# GSM_Velvet_Controller.net
KiCad netlist of a schematic drawn in Altium Designer
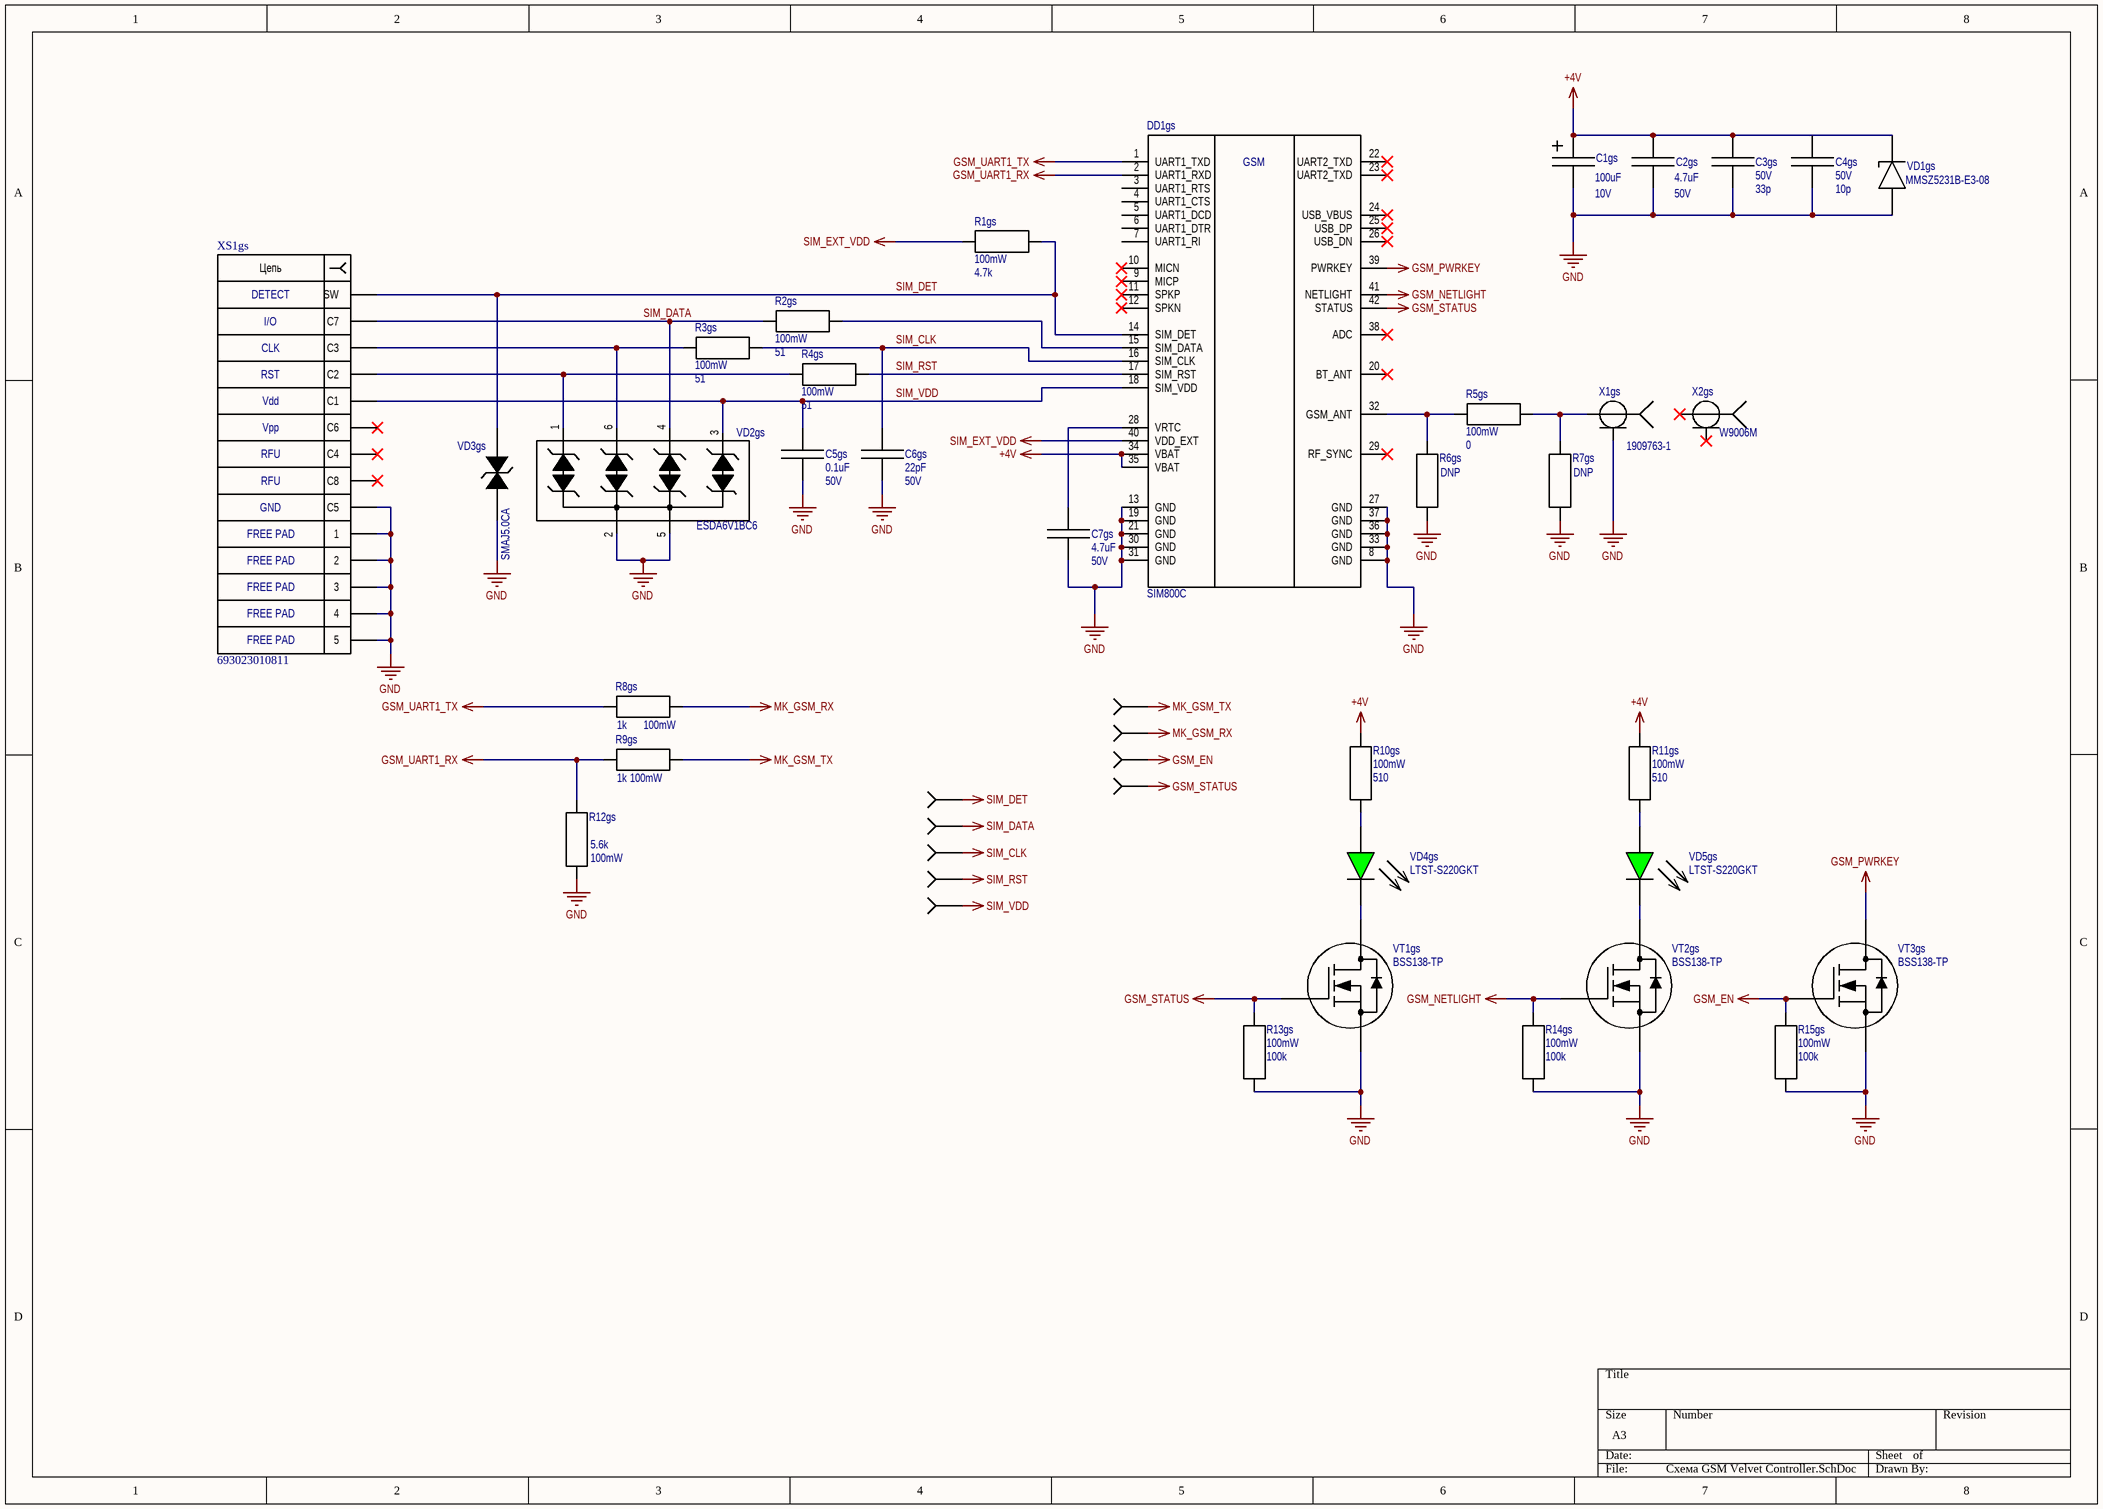
[diagram p0: Схема GSM Velvet Controller.SchDoc]

(export (version "E")
  (design (tool "Eeschema 10.0.6"))
  (components
    (comp (ref "C1gs")
      (value "TPSD107M010R0050")
      (footprint "CAP 2917 (D)")
      (description "CAP SMD TANT 100UF 20% 10V 2917")
      (fields
        (field (name "CAPACITANCE") "100uF")
        (field (name "TOLERANCE") "20%")
        (field (name "RATED VOLTAGE") "10V")
      )
      (libsource (lib "Passive components") (part "TPSD107M010R0050"))
    )
    (comp (ref "C2gs")
      (value "CL21A475KBQNNNE")
      (footprint "CAP 0805 IPC MAX")
      (description "CAP SMD CER 4.7UF 50V X5R 0805")
      (fields
        (field (name "TOLERANCE") "10%")
        (field (name "CAPACITANCE") "4.7uF")
        (field (name "RATED VOLTAGE") "50V")
      )
      (libsource (lib "Passive components") (part "CL21A475KBQNNNE"))
    )
    (comp (ref "C3gs")
      (value "C0603C330J5GAC7867")
      (footprint "CAP 0603 IPC MAX")
      (description "CAP SMD CER 33PF 50V C0G/NP0 0603")
      (fields
        (field (name "TOLERANCE") "5%")
        (field (name "RATED VOLTAGE") "50V")
        (field (name "CAPACITANCE") "33p")
      )
      (libsource (lib "Passive components") (part "C0603C330J5GAC7867"))
    )
    (comp (ref "C4gs")
      (value "CC0603JRNPO9BN100")
      (footprint "CAP 0603 IPC MAX")
      (description "CAP SMD CER 10PF 50V C0G/NP0 0603")
      (fields
        (field (name "TOLERANCE") "5%")
        (field (name "RATED VOLTAGE") "50V")
        (field (name "CAPACITANCE") "10p")
      )
      (libsource (lib "Passive components") (part "CC0603JRNPO9BN100"))
    )
    (comp (ref "C5gs")
      (value "GCM188R71H104KA57D")
      (footprint "CAP 0603 IPC MAX")
      (description "CAP SMD CER 0.1UF 50V X7R 0603")
      (fields
        (field (name "TOLERANCE") "10%")
        (field (name "CAPACITANCE") "0.1uF")
        (field (name "RATED VOLTAGE") "50V")
      )
      (libsource (lib "Passive components") (part "GCM188R71H104KA57D"))
    )
    (comp (ref "C6gs")
      (value "CC0603JRNPO9BN220")
      (footprint "CAP 0603 IPC MAX")
      (description "CAP SMD CER 22PF 50V NP0  0603")
      (fields
        (field (name "TOLERANCE") "5%")
        (field (name "CAPACITANCE") "22pF")
        (field (name "RATED VOLTAGE") "50V")
      )
      (libsource (lib "Passive components") (part "CC0603JRNPO9BN220"))
    )
    (comp (ref "C7gs")
      (value "CL21A475KBQNNNE")
      (footprint "CAP 0805 IPC MAX")
      (description "CAP SMD CER 4.7UF 50V X5R 0805")
      (fields
        (field (name "TOLERANCE") "10%")
        (field (name "CAPACITANCE") "4.7uF")
        (field (name "RATED VOLTAGE") "50V")
      )
      (libsource (lib "Passive components") (part "CL21A475KBQNNNE"))
    )
    (comp (ref "DD1gs")
      (value "SIM800C")
      (footprint "SIM-800C")
      (description "GSM/GPRS Module")
      (libsource (lib "Digital") (part "SIM800C"))
    )
    (comp (ref "R1gs")
      (value "RMCF0603FT4K70")
      (footprint "RES 0603 IPC MAX")
      (description "RES SMD 4.7k OHM 1% 1/10W 0603")
      (fields
        (field (name "TOLERANCE") "1%")
        (field (name "RATED POWER") "100mW")
        (field (name "RESISTANCE") "4.7k")
      )
      (libsource (lib "Passive components") (part "RMCF0603FT4K70"))
    )
    (comp (ref "R2gs")
      (value "RMCF0603FT51R0")
      (footprint "RES 0603 IPC MAX")
      (description "RES SMD 51 OHM 1% 1/10W 0603")
      (fields
        (field (name "TOLERANCE") "1%")
        (field (name "RATED POWER") "100mW")
        (field (name "RESISTANCE") "51")
      )
      (libsource (lib "Passive components") (part "RMCF0603FT51R0"))
    )
    (comp (ref "R3gs")
      (value "RMCF0603FT51R0")
      (footprint "RES 0603 IPC MAX")
      (description "RES SMD 51 OHM 1% 1/10W 0603")
      (fields
        (field (name "TOLERANCE") "1%")
        (field (name "RATED POWER") "100mW")
        (field (name "RESISTANCE") "51")
      )
      (libsource (lib "Passive components") (part "RMCF0603FT51R0"))
    )
    (comp (ref "R4gs")
      (value "RMCF0603FT51R0")
      (footprint "RES 0603 IPC MAX")
      (description "RES SMD 51 OHM 1% 1/10W 0603")
      (fields
        (field (name "TOLERANCE") "1%")
        (field (name "RATED POWER") "100mW")
        (field (name "RESISTANCE") "51")
      )
      (libsource (lib "Passive components") (part "RMCF0603FT51R0"))
    )
    (comp (ref "R5gs")
      (value "RMCF0603ZT0R00")
      (footprint "RES 0603 IPC MAX")
      (description "RES SMD 0 OHM 1% 1/10W 0603")
      (fields
        (field (name "TOLERANCE") "1%")
        (field (name "RATED POWER") "100mW")
        (field (name "RESISTANCE") "0")
      )
      (libsource (lib "Passive components") (part "RMCF0603ZT0R00"))
    )
    (comp (ref "R6gs")
      (value "DNP")
      (footprint "RES 0603 IPC MAX")
      (description "RES SMD/TH ?R (&K) OHM ?% ?W (PACKAGE)")
      (libsource (lib "Passive components") (part "RES GOST"))
    )
    (comp (ref "R7gs")
      (value "DNP")
      (footprint "RES 0603 IPC MAX")
      (description "RES SMD/TH ?R (&K) OHM ?% ?W (PACKAGE)")
      (libsource (lib "Passive components") (part "RES GOST"))
    )
    (comp (ref "R8gs")
      (value "RMCF0603FT1K00")
      (footprint "RES 0603 IPC MAX")
      (description "RES SMD 1K OHM 1% 1/10W 0603")
      (fields
        (field (name "RESISTANCE") "1k")
        (field (name "TOLERANCE") "1%")
        (field (name "RATED POWER") "100mW")
      )
      (libsource (lib "Passive components") (part "RMCF0603FT1K00"))
    )
    (comp (ref "R9gs")
      (value "RMCF0603FT1K00")
      (footprint "RES 0603 IPC MAX")
      (description "RES SMD 1K OHM 1% 1/10W 0603")
      (fields
        (field (name "RESISTANCE") "1k")
        (field (name "TOLERANCE") "1%")
        (field (name "RATED POWER") "100mW")
      )
      (libsource (lib "Passive components") (part "RMCF0603FT1K00"))
    )
    (comp (ref "R10gs")
      (value "RMCF0603JT510R")
      (footprint "RES 0603 IPC MAX")
      (description "RES SMD 510 OHM 5% 1/10W 0603")
      (fields
        (field (name "TOLERANCE") "5%")
        (field (name "POWER RATED") "100mW")
        (field (name "RESISTANCE") "510")
      )
      (libsource (lib "Passive components") (part "RMCF0603JT510R"))
    )
    (comp (ref "R11gs")
      (value "RMCF0603JT510R")
      (footprint "RES 0603 IPC MAX")
      (description "RES SMD 510 OHM 5% 1/10W 0603")
      (fields
        (field (name "TOLERANCE") "5%")
        (field (name "POWER RATED") "100mW")
        (field (name "RESISTANCE") "510")
      )
      (libsource (lib "Passive components") (part "RMCF0603JT510R"))
    )
    (comp (ref "R12gs")
      (value "RMCF0603FT5K60")
      (footprint "RES 0603 IPC MAX")
      (description "RES SMD 5.6K OHM 1% 1/10W 0603")
      (fields
        (field (name "RESISTANCE") "5.6k")
        (field (name "TOLERANCE") "1%")
        (field (name "RATED POWER") "100mW")
      )
      (libsource (lib "Passive components") (part "RMCF0603FT5K60"))
    )
    (comp (ref "R13gs")
      (value "RMCF0603FT100K")
      (footprint "RES 0603 IPC MAX")
      (description "RES SMD 100K OHM 5% 1/10W 0603")
      (fields
        (field (name "TOLERANCE") "5%")
        (field (name "POWER RATED") "100mW")
        (field (name "RESISTANCE") "100k")
      )
      (libsource (lib "Passive components") (part "RMCF0603FT100K"))
    )
    (comp (ref "R14gs")
      (value "RMCF0603FT100K")
      (footprint "RES 0603 IPC MAX")
      (description "RES SMD 100K OHM 5% 1/10W 0603")
      (fields
        (field (name "TOLERANCE") "5%")
        (field (name "POWER RATED") "100mW")
        (field (name "RESISTANCE") "100k")
      )
      (libsource (lib "Passive components") (part "RMCF0603FT100K"))
    )
    (comp (ref "R15gs")
      (value "RMCF0603FT100K")
      (footprint "RES 0603 IPC MAX")
      (description "RES SMD 100K OHM 5% 1/10W 0603")
      (fields
        (field (name "TOLERANCE") "5%")
        (field (name "POWER RATED") "100mW")
        (field (name "RESISTANCE") "100k")
      )
      (libsource (lib "Passive components") (part "RMCF0603FT100K"))
    )
    (comp (ref "TP2gs")
      (value "1.2MM TP")
      (footprint "TESTPOINT 1.2mm")
      (libsource (lib "Connectors") (part "Testpoint 1.2mm"))
    )
    (comp (ref "TP4gs")
      (value "1.2MM TP")
      (footprint "TESTPOINT 1.2mm")
      (libsource (lib "Connectors") (part "Testpoint 1.2mm"))
    )
    (comp (ref "TP5gs")
      (value "1.2MM TP")
      (footprint "TESTPOINT 1.2mm")
      (libsource (lib "Connectors") (part "Testpoint 1.2mm"))
    )
    (comp (ref "TP6gs")
      (value "1.2MM TP")
      (footprint "TESTPOINT 1.2mm")
      (libsource (lib "Connectors") (part "Testpoint 1.2mm"))
    )
    (comp (ref "TP7gs")
      (value "1.2MM TP")
      (footprint "TESTPOINT 1.2mm")
      (libsource (lib "Connectors") (part "Testpoint 1.2mm"))
    )
    (comp (ref "TP9gs")
      (value "1.2MM TP")
      (footprint "TESTPOINT 1.2mm")
      (libsource (lib "Connectors") (part "Testpoint 1.2mm"))
    )
    (comp (ref "TP10gs")
      (value "1.2MM TP")
      (footprint "TESTPOINT 1.2mm")
      (libsource (lib "Connectors") (part "Testpoint 1.2mm"))
    )
    (comp (ref "TP11gs")
      (value "1.2MM TP")
      (footprint "TESTPOINT 1.2mm")
      (libsource (lib "Connectors") (part "Testpoint 1.2mm"))
    )
    (comp (ref "TP12gs")
      (value "1.2MM TP")
      (footprint "TESTPOINT 1.2mm")
      (libsource (lib "Connectors") (part "Testpoint 1.2mm"))
    )
    (comp (ref "VD1gs")
      (value "MMSZ5231B-E3-08")
      (footprint "SOD-123 (Marked)")
      (description "DIODE ZENER 5.1V 500MW SOD123")
      (fields (field (name "TOLERANCE") "5%"))
      (libsource (lib "Diodes") (part "MMSZ5231B-E3-08"))
    )
    (comp (ref "VD2gs")
      (value "ESDA6V1BC6")
      (footprint "SOT-23-6")
      (description "TVS DIODE 5VWM SOT23-6")
      (libsource (lib "Diodes") (part "ESDA6V1BC6"))
    )
    (comp (ref "VD3gs")
      (value "SMAJ5.0CA")
      (footprint "DO-214AC Bidirectional")
      (description "TVS DIODE 5VWM 9.2VC DO214AC")
      (libsource (lib "Diodes") (part "SMAJ5.0CA"))
    )
    (comp (ref "VD4gs")
      (value "LTST-S220GKT")
      (footprint "0805 DIODE")
      (description "LED GREEN CLEAR SMD R/A")
      (libsource (lib "Diodes") (part "LTST-S220GKT"))
    )
    (comp (ref "VD5gs")
      (value "LTST-S220GKT")
      (footprint "0805 DIODE")
      (description "LED GREEN CLEAR SMD R/A")
      (libsource (lib "Diodes") (part "LTST-S220GKT"))
    )
    (comp (ref "VT1gs")
      (value "BSS138-TP")
      (footprint "SOT-23-3")
      (description "MOSFET N-CH 50V 220MA SOT23")
      (libsource (lib "MOSFET") (part "BSS138-TP"))
    )
    (comp (ref "VT2gs")
      (value "BSS138-TP")
      (footprint "SOT-23-3")
      (description "MOSFET N-CH 50V 220MA SOT23")
      (libsource (lib "MOSFET") (part "BSS138-TP"))
    )
    (comp (ref "VT3gs")
      (value "BSS138-TP")
      (footprint "SOT-23-3")
      (description "MOSFET N-CH 50V 220MA SOT23")
      (libsource (lib "MOSFET") (part "BSS138-TP"))
    )
    (comp (ref "X1gs")
      (value "1909763-1")
      (footprint "1909763-1")
      (description "CONN UMCC JACK STR 50OHM SMD")
      (libsource (lib "Connectors") (part "1909763-1"))
    )
    (comp (ref "X2gs")
      (value "W9006M")
      (description "CABLE ASSY 6\" SMA FM TO I-PEX")
      (libsource (lib "Connectors") (part "W9006M"))
    )
    (comp (ref "XS1gs")
      (value "693023010811")
      (footprint "693023010811")
      (description "CONN SMART CARD")
      (libsource (lib "Connectors") (part "693023010811"))
    )
  )
  (nets
    (net (code "1") (name "+4V") (class "Default")
      (node (ref "C1gs") (pin "1") (pinfunction "1_1") (pintype "passive"))
      (node (ref "C2gs") (pin "1") (pinfunction "1_1") (pintype "passive"))
      (node (ref "C3gs") (pin "1") (pinfunction "1_1") (pintype "passive"))
      (node (ref "C4gs") (pin "1") (pinfunction "1_1") (pintype "passive"))
      (node (ref "DD1gs") (pin "34") (pinfunction "VBAT_34") (pintype "passive"))
      (node (ref "DD1gs") (pin "35") (pinfunction "VBAT_35") (pintype "passive"))
      (node (ref "R10gs") (pin "2") (pinfunction "2_2") (pintype "passive"))
      (node (ref "R11gs") (pin "2") (pinfunction "2_2") (pintype "passive"))
      (node (ref "VD1gs") (pin "1") (pinfunction "1_1") (pintype "passive"))
    )
    (net (code "2") (name "GND") (class "Default")
      (node (ref "C1gs") (pin "2") (pinfunction "2_2") (pintype "passive"))
      (node (ref "C2gs") (pin "2") (pinfunction "2_2") (pintype "passive"))
      (node (ref "C3gs") (pin "2") (pinfunction "2_2") (pintype "passive"))
      (node (ref "C4gs") (pin "2") (pinfunction "2_2") (pintype "passive"))
      (node (ref "C5gs") (pin "2") (pinfunction "2_2") (pintype "passive"))
      (node (ref "C6gs") (pin "2") (pinfunction "2_2") (pintype "passive"))
      (node (ref "C7gs") (pin "2") (pinfunction "2_2") (pintype "passive"))
      (node (ref "DD1gs") (pin "13") (pinfunction "GND_13") (pintype "passive"))
      (node (ref "DD1gs") (pin "19") (pinfunction "GND_19") (pintype "passive"))
      (node (ref "DD1gs") (pin "21") (pinfunction "GND_21") (pintype "passive"))
      (node (ref "DD1gs") (pin "27") (pinfunction "GND_27") (pintype "passive"))
      (node (ref "DD1gs") (pin "30") (pinfunction "GND_30") (pintype "passive"))
      (node (ref "DD1gs") (pin "31") (pinfunction "GND_31") (pintype "passive"))
      (node (ref "DD1gs") (pin "33") (pinfunction "GND_33") (pintype "passive"))
      (node (ref "DD1gs") (pin "36") (pinfunction "GND_36") (pintype "passive"))
      (node (ref "DD1gs") (pin "37") (pinfunction "GND_37") (pintype "passive"))
      (node (ref "DD1gs") (pin "8") (pinfunction "GND_8") (pintype "passive"))
      (node (ref "R12gs") (pin "1") (pinfunction "1_1") (pintype "passive"))
      (node (ref "R13gs") (pin "1") (pinfunction "1_1") (pintype "passive"))
      (node (ref "R14gs") (pin "1") (pinfunction "1_1") (pintype "passive"))
      (node (ref "R15gs") (pin "1") (pinfunction "1_1") (pintype "passive"))
      (node (ref "R6gs") (pin "1") (pinfunction "1_1") (pintype "passive"))
      (node (ref "R7gs") (pin "1") (pinfunction "1_1") (pintype "passive"))
      (node (ref "VD1gs") (pin "2") (pinfunction "2_2") (pintype "passive"))
      (node (ref "VD2gs") (pin "2") (pinfunction "2_2") (pintype "passive"))
      (node (ref "VD2gs") (pin "5") (pinfunction "5_5") (pintype "passive"))
      (node (ref "VD3gs") (pin "1") (pinfunction "1_1") (pintype "passive"))
      (node (ref "VT1gs") (pin "2") (pinfunction "S_2") (pintype "passive"))
      (node (ref "VT2gs") (pin "2") (pinfunction "S_2") (pintype "passive"))
      (node (ref "VT3gs") (pin "2") (pinfunction "S_2") (pintype "passive"))
      (node (ref "X1gs") (pin "2") (pinfunction "2_2") (pintype "passive"))
      (node (ref "XS1gs") (pin "1") (pinfunction "1_1") (pintype "passive"))
      (node (ref "XS1gs") (pin "2") (pinfunction "2_2") (pintype "passive"))
      (node (ref "XS1gs") (pin "3") (pinfunction "3_3") (pintype "passive"))
      (node (ref "XS1gs") (pin "4") (pinfunction "4_4") (pintype "passive"))
      (node (ref "XS1gs") (pin "5") (pinfunction "5_5") (pintype "passive"))
      (node (ref "XS1gs") (pin "C5") (pinfunction "C5_C5") (pintype "passive"))
    )
    (net (code "3") (name "GSM_EN") (class "Default")
      (node (ref "R15gs") (pin "2") (pinfunction "2_2") (pintype "passive"))
      (node (ref "TP5gs") (pin "1") (pinfunction "1_1") (pintype "passive"))
      (node (ref "VT3gs") (pin "1") (pinfunction "G_1") (pintype "passive"))
    )
    (net (code "4") (name "GSM_NETLIGHT") (class "Default")
      (node (ref "DD1gs") (pin "41") (pinfunction "NETLIGHT_41") (pintype "passive"))
      (node (ref "R14gs") (pin "2") (pinfunction "2_2") (pintype "passive"))
      (node (ref "VT2gs") (pin "1") (pinfunction "G_1") (pintype "passive"))
    )
    (net (code "5") (name "GSM_PWRKEY") (class "Default")
      (node (ref "DD1gs") (pin "39") (pinfunction "PWRKEY_39") (pintype "passive"))
      (node (ref "VT3gs") (pin "3") (pinfunction "D_3") (pintype "passive"))
    )
    (net (code "6") (name "GSM_STATUS") (class "Default")
      (node (ref "DD1gs") (pin "42") (pinfunction "STATUS_42") (pintype "passive"))
      (node (ref "R13gs") (pin "2") (pinfunction "2_2") (pintype "passive"))
      (node (ref "TP6gs") (pin "1") (pinfunction "1_1") (pintype "passive"))
      (node (ref "VT1gs") (pin "1") (pinfunction "G_1") (pintype "passive"))
    )
    (net (code "7") (name "GSM_UART1_RX") (class "Default")
      (node (ref "DD1gs") (pin "2") (pinfunction "UART1_RXD_2") (pintype "passive"))
      (node (ref "R12gs") (pin "2") (pinfunction "2_2") (pintype "passive"))
      (node (ref "R9gs") (pin "1") (pinfunction "1_1") (pintype "passive"))
    )
    (net (code "8") (name "GSM_UART1_TX") (class "Default")
      (node (ref "DD1gs") (pin "1") (pinfunction "UART1_TXD_1") (pintype "passive"))
      (node (ref "R8gs") (pin "1") (pinfunction "1_1") (pintype "passive"))
    )
    (net (code "9") (name "MK_GSM_RX") (class "Default")
      (node (ref "R8gs") (pin "2") (pinfunction "2_2") (pintype "passive"))
      (node (ref "TP4gs") (pin "1") (pinfunction "1_1") (pintype "passive"))
    )
    (net (code "10") (name "MK_GSM_TX") (class "Default")
      (node (ref "R9gs") (pin "2") (pinfunction "2_2") (pintype "passive"))
      (node (ref "TP2gs") (pin "1") (pinfunction "1_1") (pintype "passive"))
    )
    (net (code "11") (name "Net-(DD1gs-GSM_ANT)") (class "Default")
      (node (ref "DD1gs") (pin "32") (pinfunction "GSM_ANT_32") (pintype "passive"))
      (node (ref "R5gs") (pin "1") (pinfunction "1_1") (pintype "passive"))
      (node (ref "R6gs") (pin "2") (pinfunction "2_2") (pintype "passive"))
    )
    (net (code "12") (name "Net-(DD1gs-SIM_DATA)") (class "Default")
      (node (ref "DD1gs") (pin "15") (pinfunction "SIM_DATA_15") (pintype "passive"))
      (node (ref "R2gs") (pin "2") (pinfunction "2_2") (pintype "passive"))
    )
    (net (code "13") (name "Net-(DD1gs-VRTC)") (class "Default")
      (node (ref "C7gs") (pin "1") (pinfunction "1_1") (pintype "passive"))
      (node (ref "DD1gs") (pin "28") (pinfunction "VRTC_28") (pintype "passive"))
    )
    (net (code "14") (name "Net-(R3gs-Pad1)") (class "Default")
      (node (ref "R3gs") (pin "1") (pinfunction "1_1") (pintype "passive"))
      (node (ref "VD2gs") (pin "6") (pinfunction "6_6") (pintype "passive"))
      (node (ref "XS1gs") (pin "C3") (pinfunction "C3_C3") (pintype "passive"))
    )
    (net (code "15") (name "Net-(R4gs-Pad1)") (class "Default")
      (node (ref "R4gs") (pin "1") (pinfunction "1_1") (pintype "passive"))
      (node (ref "VD2gs") (pin "1") (pinfunction "1_1") (pintype "passive"))
      (node (ref "XS1gs") (pin "C2") (pinfunction "C2_C2") (pintype "passive"))
    )
    (net (code "16") (name "Net-(R5gs-Pad2)") (class "Default")
      (node (ref "R5gs") (pin "2") (pinfunction "2_2") (pintype "passive"))
      (node (ref "R7gs") (pin "2") (pinfunction "2_2") (pintype "passive"))
      (node (ref "X1gs") (pin "1") (pinfunction "1_1") (pintype "passive"))
    )
    (net (code "17") (name "Net-(R10gs-Pad1)") (class "Default")
      (node (ref "R10gs") (pin "1") (pinfunction "1_1") (pintype "passive"))
      (node (ref "VD4gs") (pin "1") (pinfunction "1_1") (pintype "passive"))
    )
    (net (code "18") (name "Net-(R11gs-Pad1)") (class "Default")
      (node (ref "R11gs") (pin "1") (pinfunction "1_1") (pintype "passive"))
      (node (ref "VD5gs") (pin "1") (pinfunction "1_1") (pintype "passive"))
    )
    (net (code "19") (name "Net-(VT1gs-D)") (class "Default")
      (node (ref "VD4gs") (pin "2") (pinfunction "2_2") (pintype "passive"))
      (node (ref "VT1gs") (pin "3") (pinfunction "D_3") (pintype "passive"))
    )
    (net (code "20") (name "Net-(VT2gs-D)") (class "Default")
      (node (ref "VD5gs") (pin "2") (pinfunction "2_2") (pintype "passive"))
      (node (ref "VT2gs") (pin "3") (pinfunction "D_3") (pintype "passive"))
    )
    (net (code "21") (name "SIM_CLK") (class "Default")
      (node (ref "C6gs") (pin "1") (pinfunction "1_1") (pintype "passive"))
      (node (ref "DD1gs") (pin "16") (pinfunction "SIM_CLK_16") (pintype "passive"))
      (node (ref "R3gs") (pin "2") (pinfunction "2_2") (pintype "passive"))
      (node (ref "TP10gs") (pin "1") (pinfunction "1_1") (pintype "passive"))
    )
    (net (code "22") (name "SIM_DATA") (class "Default")
      (node (ref "R2gs") (pin "1") (pinfunction "1_1") (pintype "passive"))
      (node (ref "TP9gs") (pin "1") (pinfunction "1_1") (pintype "passive"))
      (node (ref "VD2gs") (pin "4") (pinfunction "4_4") (pintype "passive"))
      (node (ref "XS1gs") (pin "C7") (pinfunction "C7_C7") (pintype "passive"))
    )
    (net (code "23") (name "SIM_DET") (class "Default")
      (node (ref "DD1gs") (pin "14") (pinfunction "SIM_DET_14") (pintype "passive"))
      (node (ref "R1gs") (pin "2") (pinfunction "2_2") (pintype "passive"))
      (node (ref "TP7gs") (pin "1") (pinfunction "1_1") (pintype "passive"))
      (node (ref "VD3gs") (pin "2") (pinfunction "2_2") (pintype "passive"))
      (node (ref "XS1gs") (pin "SW") (pinfunction "SW_SW") (pintype "passive"))
    )
    (net (code "24") (name "SIM_EXT_VDD") (class "Default")
      (node (ref "DD1gs") (pin "40") (pinfunction "VDD_EXT_40") (pintype "passive"))
      (node (ref "R1gs") (pin "1") (pinfunction "1_1") (pintype "passive"))
    )
    (net (code "25") (name "SIM_RST") (class "Default")
      (node (ref "DD1gs") (pin "17") (pinfunction "SIM_RST_17") (pintype "passive"))
      (node (ref "R4gs") (pin "2") (pinfunction "2_2") (pintype "passive"))
      (node (ref "TP11gs") (pin "1") (pinfunction "1_1") (pintype "passive"))
    )
    (net (code "26") (name "SIM_VDD") (class "Default")
      (node (ref "C5gs") (pin "1") (pinfunction "1_1") (pintype "passive"))
      (node (ref "DD1gs") (pin "18") (pinfunction "SIM_VDD_18") (pintype "passive"))
      (node (ref "TP12gs") (pin "1") (pinfunction "1_1") (pintype "passive"))
      (node (ref "VD2gs") (pin "3") (pinfunction "3_3") (pintype "passive"))
      (node (ref "XS1gs") (pin "C1") (pinfunction "C1_C1") (pintype "passive"))
    )
    (net (code "27") (name "unconnected-(DD1gs-ADC-Pad38)") (class "Default")
      (node (ref "DD1gs") (pin "38") (pinfunction "ADC_38") (pintype "passive+no_connect"))
    )
    (net (code "28") (name "unconnected-(DD1gs-BT_ANT-Pad20)") (class "Default")
      (node (ref "DD1gs") (pin "20") (pinfunction "BT_ANT_20") (pintype "passive+no_connect"))
    )
    (net (code "29") (name "unconnected-(DD1gs-MICN-Pad10)") (class "Default")
      (node (ref "DD1gs") (pin "10") (pinfunction "MICN_10") (pintype "passive+no_connect"))
    )
    (net (code "30") (name "unconnected-(DD1gs-MICP-Pad9)") (class "Default")
      (node (ref "DD1gs") (pin "9") (pinfunction "MICP_9") (pintype "passive+no_connect"))
    )
    (net (code "31") (name "unconnected-(DD1gs-RF_SYNC-Pad29)") (class "Default")
      (node (ref "DD1gs") (pin "29") (pinfunction "RF_SYNC_29") (pintype "passive+no_connect"))
    )
    (net (code "32") (name "unconnected-(DD1gs-SPKN-Pad12)") (class "Default")
      (node (ref "DD1gs") (pin "12") (pinfunction "SPKN_12") (pintype "passive+no_connect"))
    )
    (net (code "33") (name "unconnected-(DD1gs-SPKP-Pad11)") (class "Default")
      (node (ref "DD1gs") (pin "11") (pinfunction "SPKP_11") (pintype "passive+no_connect"))
    )
    (net (code "34") (name "unconnected-(DD1gs-UART1_CTS-Pad4)") (class "Default")
      (node (ref "DD1gs") (pin "4") (pinfunction "UART1_CTS_4") (pintype "passive"))
    )
    (net (code "35") (name "unconnected-(DD1gs-UART1_DCD-Pad5)") (class "Default")
      (node (ref "DD1gs") (pin "5") (pinfunction "UART1_DCD_5") (pintype "passive"))
    )
    (net (code "36") (name "unconnected-(DD1gs-UART1_DTR-Pad6)") (class "Default")
      (node (ref "DD1gs") (pin "6") (pinfunction "UART1_DTR_6") (pintype "passive"))
    )
    (net (code "37") (name "unconnected-(DD1gs-UART1_RI-Pad7)") (class "Default")
      (node (ref "DD1gs") (pin "7") (pinfunction "UART1_RI_7") (pintype "passive"))
    )
    (net (code "38") (name "unconnected-(DD1gs-UART1_RTS-Pad3)") (class "Default")
      (node (ref "DD1gs") (pin "3") (pinfunction "UART1_RTS_3") (pintype "passive"))
    )
    (net (code "39") (name "unconnected-(DD1gs-UART2_TXD-Pad22)") (class "Default")
      (node (ref "DD1gs") (pin "22") (pinfunction "UART2_TXD_22") (pintype "passive+no_connect"))
    )
    (net (code "40") (name "unconnected-(DD1gs-UART2_TXD-Pad23)") (class "Default")
      (node (ref "DD1gs") (pin "23") (pinfunction "UART2_TXD_23") (pintype "passive+no_connect"))
    )
    (net (code "41") (name "unconnected-(DD1gs-USB_DN-Pad26)") (class "Default")
      (node (ref "DD1gs") (pin "26") (pinfunction "USB_DN_26") (pintype "passive+no_connect"))
    )
    (net (code "42") (name "unconnected-(DD1gs-USB_DP-Pad25)") (class "Default")
      (node (ref "DD1gs") (pin "25") (pinfunction "USB_DP_25") (pintype "passive+no_connect"))
    )
    (net (code "43") (name "unconnected-(DD1gs-USB_VBUS-Pad24)") (class "Default")
      (node (ref "DD1gs") (pin "24") (pinfunction "USB_VBUS_24") (pintype "passive+no_connect"))
    )
    (net (code "44") (name "unconnected-(X2gs-Pad1)") (class "Default")
      (node (ref "X2gs") (pin "1") (pinfunction "1_1") (pintype "passive+no_connect"))
    )
    (net (code "45") (name "unconnected-(X2gs-Pad2)") (class "Default")
      (node (ref "X2gs") (pin "2") (pinfunction "2_2") (pintype "passive+no_connect"))
    )
    (net (code "46") (name "unconnected-(XS1gs-PadC4)") (class "Default")
      (node (ref "XS1gs") (pin "C4") (pinfunction "C4_C4") (pintype "passive+no_connect"))
    )
    (net (code "47") (name "unconnected-(XS1gs-PadC6)") (class "Default")
      (node (ref "XS1gs") (pin "C6") (pinfunction "C6_C6") (pintype "passive+no_connect"))
    )
    (net (code "48") (name "unconnected-(XS1gs-PadC8)") (class "Default")
      (node (ref "XS1gs") (pin "C8") (pinfunction "C8_C8") (pintype "passive+no_connect"))
    )
  )
)
